# PlantWaterer.net
KiCad netlist of a schematic drawn in EAGLE
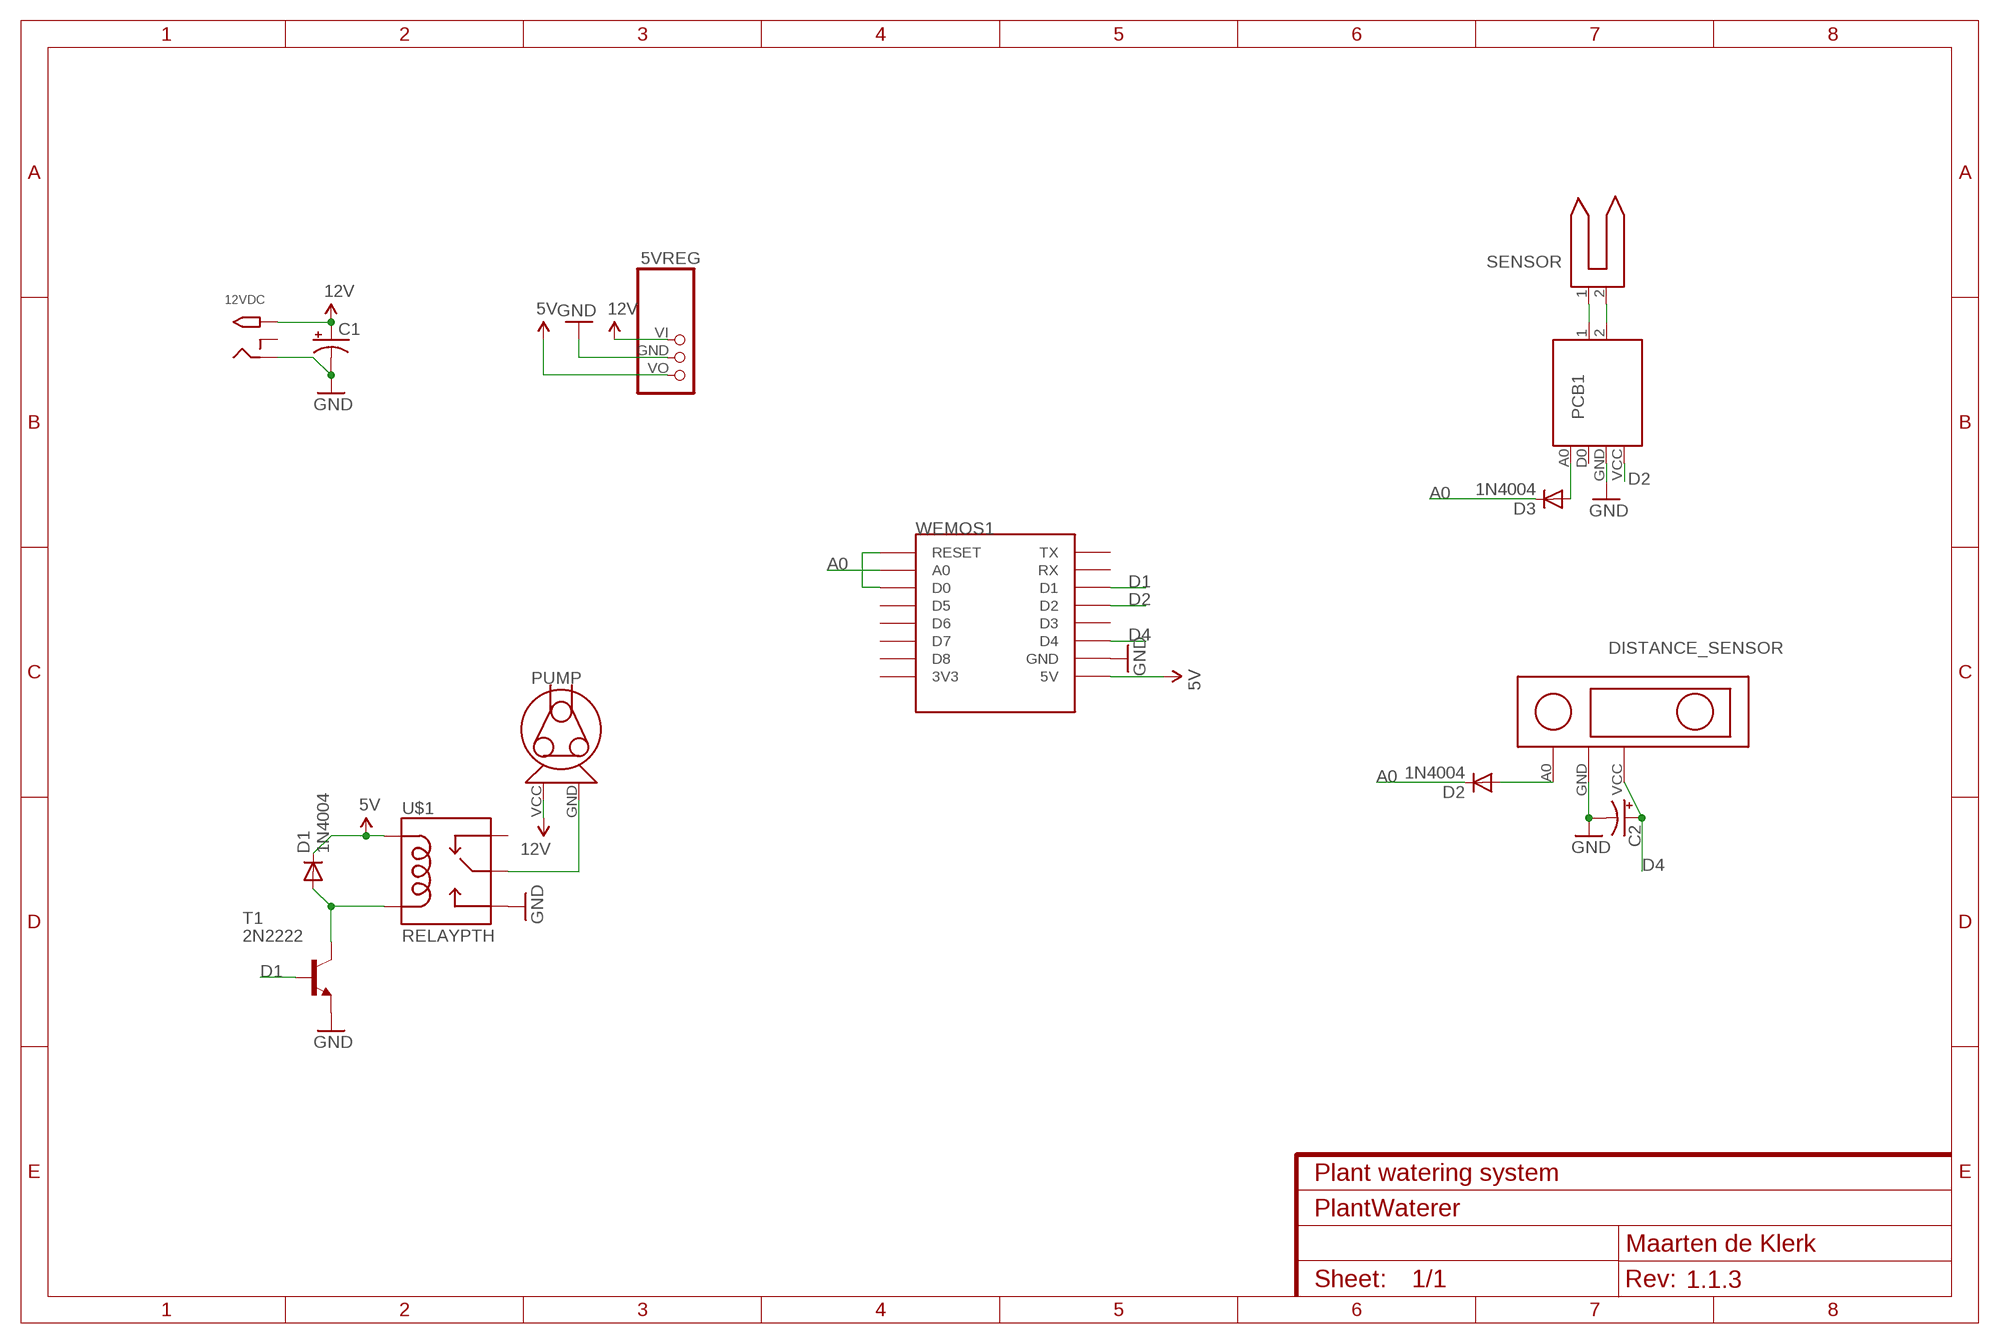
[diagram p0: schematic, sheet 1]

(export (version "E")
  (design (tool "Eeschema 10.0.6"))
  (components
    (comp (ref "5VREG")
      (value "5V_REG")
      (footprint "eagle-import:5V_REG")
      (libsource (lib "eagle-import") (part "5V_REG"))
    )
    (comp (ref "12VDC")
      (value "2.1MMJACK")
      (footprint "eagle-import:PJ-102A")
      (libsource (lib "eagle-import") (part "2.1MMJACK"))
    )
    (comp (ref "C1")
      (value "100UF-25V-20%(PTH)")
      (footprint "eagle-import:CPOL-RADIAL-100UF-25V")
      (libsource (lib "eagle-import") (part "100UF-25V-20%(PTH)"))
    )
    (comp (ref "C2")
      (value "10UF-25V-20%(PTH)")
      (footprint "eagle-import:CPOL-RADIAL-10UF-25V")
      (libsource (lib "eagle-import") (part "10UF-25V-20%(PTH)"))
    )
    (comp (ref "D1")
      (value "1N4004")
      (footprint "eagle-import:DO41-10")
      (libsource (lib "eagle-import") (part "1N4004"))
    )
    (comp (ref "D2")
      (value "1N4004")
      (footprint "eagle-import:DO41-10")
      (libsource (lib "eagle-import") (part "1N4004"))
    )
    (comp (ref "D3")
      (value "1N4004")
      (footprint "eagle-import:DO41-10")
      (libsource (lib "eagle-import") (part "1N4004"))
    )
    (comp (ref "DISTANCE_SENSOR")
      (value "SHARP_GP2Y0A21YK")
      (footprint "eagle-import:SHARP_GP2Y0A21YK")
      (libsource (lib "eagle-import") (part "SHARP_GP2Y0A21YK"))
    )
    (comp (ref "PCB1")
      (value "WATER_SENSOR_PCB")
      (footprint "eagle-import:WATER_SENSOR_PCB")
      (libsource (lib "eagle-import") (part "WATER_SENSOR_PCB"))
    )
    (comp (ref "PUMP")
      (value "PERISTALTIC_PUMP")
      (footprint "eagle-import:PERISTALTIC_PUMP")
      (libsource (lib "eagle-import") (part "PERISTALTIC_PUMP"))
    )
    (comp (ref "SENSOR")
      (value "WATER_SENSOR")
      (footprint "eagle-import:WATER_SENSOR")
      (libsource (lib "eagle-import") (part "WATER_SENSOR"))
    )
    (comp (ref "T1")
      (value "2N2222")
      (footprint "eagle-import:TO92-EBC-OVAL")
      (libsource (lib "eagle-import") (part "2N2222"))
    )
    (comp (ref "U$1")
      (value "RELAYPTH")
      (footprint "eagle-import:SRD-05VDC-SL-C")
      (libsource (lib "eagle-import") (part "RELAYPTH"))
    )
    (comp (ref "WEMOS1")
      (value "WEMOS-D1-MINI")
      (footprint "eagle-import:WEMOS-D1-MINI")
      (libsource (lib "eagle-import") (part "WEMOS-D1-MINI"))
    )
  )
  (nets
    (net (code "1") (name "/A0") (class "Default")
      (node (ref "D2") (pin "C") (pinfunction "C_C") (pintype "passive"))
      (node (ref "D3") (pin "C") (pinfunction "C_C") (pintype "passive"))
      (node (ref "WEMOS1") (pin "A0") (pinfunction "A0_A0") (pintype "bidirectional"))
    )
    (net (code "2") (name "/D1") (class "Default")
      (node (ref "T1") (pin "B") (pinfunction "B_B") (pintype "passive"))
      (node (ref "WEMOS1") (pin "D1") (pinfunction "D1_D1") (pintype "bidirectional"))
    )
    (net (code "3") (name "/D2") (class "Default")
      (node (ref "PCB1") (pin "VCC") (pinfunction "VCC_VCC") (pintype "passive"))
      (node (ref "WEMOS1") (pin "D2") (pinfunction "D2_D2") (pintype "bidirectional"))
    )
    (net (code "4") (name "/D4") (class "Default")
      (node (ref "C2") (pin "1") (pinfunction "+_1") (pintype "passive"))
      (node (ref "DISTANCE_SENSOR") (pin "VCC") (pinfunction "VCC_VCC") (pintype "input"))
      (node (ref "WEMOS1") (pin "D4") (pinfunction "D4_D4") (pintype "bidirectional"))
    )
    (net (code "5") (name "5V") (class "Default")
      (node (ref "5VREG") (pin "VO") (pinfunction "VO_VO") (pintype "passive"))
      (node (ref "D1") (pin "C") (pinfunction "C_C") (pintype "passive"))
      (node (ref "U$1") (pin "COIL1") (pinfunction "COIL1_COIL1") (pintype "bidirectional"))
      (node (ref "WEMOS1") (pin "5V") (pinfunction "5V_5V") (pintype "bidirectional"))
    )
    (net (code "6") (name "12V") (class "Default")
      (node (ref "12VDC") (pin "TIP") (pinfunction "TIP_TIP") (pintype "bidirectional"))
      (node (ref "5VREG") (pin "VI") (pinfunction "VI_VI") (pintype "passive"))
      (node (ref "C1") (pin "1") (pinfunction "+_1") (pintype "passive"))
      (node (ref "PUMP") (pin "VCC") (pinfunction "VCC_VCC") (pintype "input"))
    )
    (net (code "7") (name "GND") (class "Default")
      (node (ref "12VDC") (pin "RING") (pinfunction "RING_RING") (pintype "bidirectional"))
      (node (ref "5VREG") (pin "GND") (pinfunction "GND_GND") (pintype "passive"))
      (node (ref "C1") (pin "2") (pinfunction "-_2") (pintype "passive"))
      (node (ref "C2") (pin "2") (pinfunction "-_2") (pintype "passive"))
      (node (ref "DISTANCE_SENSOR") (pin "GND") (pinfunction "GND_GND") (pintype "output"))
      (node (ref "PCB1") (pin "GND") (pinfunction "GND_GND") (pintype "passive"))
      (node (ref "T1") (pin "E") (pinfunction "E_E") (pintype "passive"))
      (node (ref "U$1") (pin "SWOPEN") (pinfunction "SWOPEN_SWOPEN") (pintype "bidirectional"))
      (node (ref "WEMOS1") (pin "GND") (pinfunction "GND_GND") (pintype "bidirectional"))
    )
    (net (code "8") (name "Net-(D1-PadA)") (class "Default")
      (node (ref "D1") (pin "A") (pinfunction "A_A") (pintype "passive"))
      (node (ref "T1") (pin "C") (pinfunction "C_C") (pintype "passive"))
      (node (ref "U$1") (pin "COIL0") (pinfunction "COIL0_COIL0") (pintype "bidirectional"))
    )
    (net (code "9") (name "Net-(D2-PadA)") (class "Default")
      (node (ref "D2") (pin "A") (pinfunction "A_A") (pintype "passive"))
      (node (ref "DISTANCE_SENSOR") (pin "A0") (pinfunction "A0_A0") (pintype "bidirectional"))
    )
    (net (code "10") (name "Net-(D3-PadA)") (class "Default")
      (node (ref "D3") (pin "A") (pinfunction "A_A") (pintype "passive"))
      (node (ref "PCB1") (pin "A0") (pinfunction "A0_A0") (pintype "passive"))
    )
    (net (code "11") (name "Net-(PCB1-Pad1)") (class "Default")
      (node (ref "PCB1") (pin "1") (pinfunction "1_1") (pintype "bidirectional"))
      (node (ref "SENSOR") (pin "1") (pinfunction "1_1") (pintype "passive"))
    )
    (net (code "12") (name "Net-(PCB1-Pad2)") (class "Default")
      (node (ref "PCB1") (pin "2") (pinfunction "2_2") (pintype "bidirectional"))
      (node (ref "SENSOR") (pin "2") (pinfunction "2_2") (pintype "passive"))
    )
    (net (code "13") (name "Net-(PUMP-PadGND)") (class "Default")
      (node (ref "PUMP") (pin "GND") (pinfunction "GND_GND") (pintype "output"))
      (node (ref "U$1") (pin "SWCOMMON") (pinfunction "SWCOMMON_SWCOMMON") (pintype "bidirectional"))
    )
    (net (code "14") (name "Net-(WEMOS1-PadD0)") (class "Default")
      (node (ref "WEMOS1") (pin "D0") (pinfunction "D0_D0") (pintype "bidirectional"))
      (node (ref "WEMOS1") (pin "RESET") (pinfunction "RESET_RESET") (pintype "bidirectional"))
    )
    (net (code "15") (name "unconnected-(12VDC-PadRING_SW)") (class "Default")
      (node (ref "12VDC") (pin "RING_SW") (pinfunction "RING_SW_RING_SW") (pintype "bidirectional"))
    )
    (net (code "16") (name "unconnected-(PCB1-PadD0)") (class "Default")
      (node (ref "PCB1") (pin "D0") (pinfunction "D0_D0") (pintype "passive"))
    )
    (net (code "17") (name "unconnected-(U$1-SWCLOSE-PadSWCLOSED)") (class "Default")
      (node (ref "U$1") (pin "SWCLOSED") (pinfunction "SWCLOSE_SWCLOSED") (pintype "bidirectional"))
    )
    (net (code "18") (name "unconnected-(WEMOS1-Pad3V3)") (class "Default")
      (node (ref "WEMOS1") (pin "3V3") (pinfunction "3V3_3V3") (pintype "bidirectional"))
    )
    (net (code "19") (name "unconnected-(WEMOS1-PadD3)") (class "Default")
      (node (ref "WEMOS1") (pin "D3") (pinfunction "D3_D3") (pintype "bidirectional"))
    )
    (net (code "20") (name "unconnected-(WEMOS1-PadD5)") (class "Default")
      (node (ref "WEMOS1") (pin "D5") (pinfunction "D5_D5") (pintype "bidirectional"))
    )
    (net (code "21") (name "unconnected-(WEMOS1-PadD6)") (class "Default")
      (node (ref "WEMOS1") (pin "D6") (pinfunction "D6_D6") (pintype "bidirectional"))
    )
    (net (code "22") (name "unconnected-(WEMOS1-PadD7)") (class "Default")
      (node (ref "WEMOS1") (pin "D7") (pinfunction "D7_D7") (pintype "bidirectional"))
    )
    (net (code "23") (name "unconnected-(WEMOS1-PadD8)") (class "Default")
      (node (ref "WEMOS1") (pin "D8") (pinfunction "D8_D8") (pintype "bidirectional"))
    )
    (net (code "24") (name "unconnected-(WEMOS1-PadRX)") (class "Default")
      (node (ref "WEMOS1") (pin "RX") (pinfunction "RX_RX") (pintype "bidirectional"))
    )
    (net (code "25") (name "unconnected-(WEMOS1-PadTX)") (class "Default")
      (node (ref "WEMOS1") (pin "TX") (pinfunction "TX_TX") (pintype "bidirectional"))
    )
  )
)
